# Sensors.net
KiCad netlist of a schematic drawn in Altium Designer
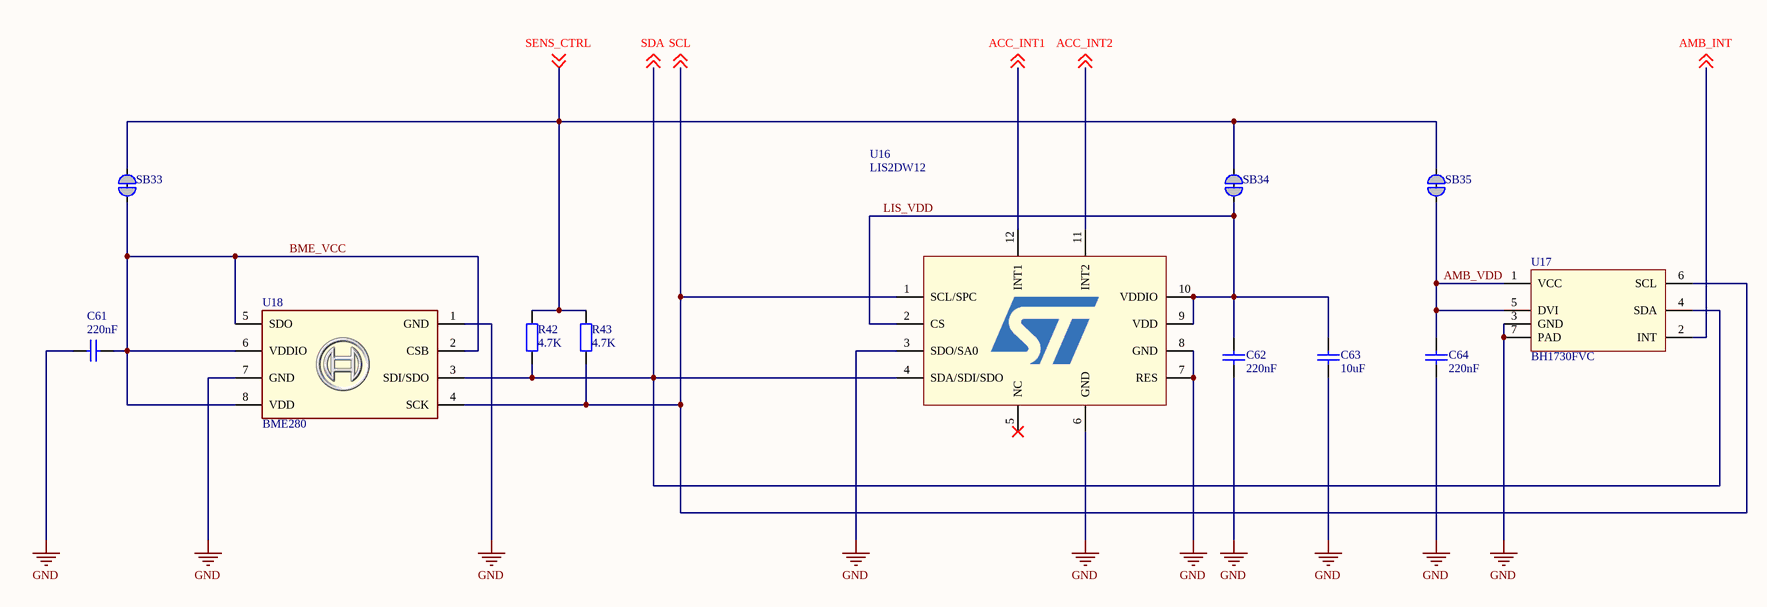
[diagram p0: Sensors.SchDoc]

(export (version "E")
  (design (tool "Eeschema 10.0.6"))
  (components
    (comp (ref "C61")
      (value "220nF")
      (footprint "C0402")
      (description "Capacitor (Semiconductor SIM Model)")
      (fields
        (field (name "MANUFACTURER") "YAGEO")
        (field (name "MANUFACTURER PART NO.") "CC0402KRX5R5BB224")
      )
      (libsource (lib "Miscellaneous Devices") (part "Cap Semi"))
    )
    (comp (ref "C62")
      (value "220nF")
      (footprint "C0402")
      (description "Capacitor (Semiconductor SIM Model)")
      (fields
        (field (name "MANUFACTURER") "YAGEO")
        (field (name "MANUFACTURER PART NO.") "CC0402KRX5R5BB224")
      )
      (libsource (lib "Miscellaneous Devices") (part "Cap Semi"))
    )
    (comp (ref "C63")
      (value "10uF")
      (footprint "C0402")
      (description "Capacitor (Semiconductor SIM Model)")
      (fields
        (field (name "MANUFACTURER") "YAGEO")
        (field (name "MANUFACTURER PART NO.") "CC0402KRX5R5BB224")
      )
      (libsource (lib "Miscellaneous Devices") (part "Cap Semi"))
    )
    (comp (ref "C64")
      (value "220nF")
      (footprint "C0402")
      (description "Capacitor (Semiconductor SIM Model)")
      (fields
        (field (name "MANUFACTURER") "YAGEO")
        (field (name "MANUFACTURER PART NO.") "CC0402KRX5R5BB224")
      )
      (libsource (lib "Miscellaneous Devices") (part "Cap Semi"))
    )
    (comp (ref "R42")
      (value "4.7K")
      (footprint "R0402")
      (fields
        (field (name "MANUFACTURER") "ASJ")
        (field (name "MANUFACTURER PART NO.") "CR10-472-JK")
        (field (name "Comment") "Res2")
      )
      (libsource (lib "Miscellaneous Devices") (part "Res2"))
    )
    (comp (ref "R43")
      (value "4.7K")
      (footprint "R0402")
      (fields
        (field (name "MANUFACTURER") "ASJ")
        (field (name "MANUFACTURER PART NO.") "CR10-472-JK")
        (field (name "Comment") "Res2")
      )
      (libsource (lib "Miscellaneous Devices") (part "Res2"))
    )
    (comp (ref "SB33")
      (value "Solderbridge")
      (footprint "Solderbridge_Shorted")
      (libsource (lib "altium-import") (part "root_1_SOLDERBRIDGE_SHORTED_"))
    )
    (comp (ref "SB34")
      (value "Solderbridge")
      (footprint "Solderbridge_Shorted")
      (libsource (lib "altium-import") (part "root_1_SOLDERBRIDGE_SHORTED_"))
    )
    (comp (ref "SB35")
      (value "Solderbridge")
      (footprint "Solderbridge_Shorted")
      (libsource (lib "altium-import") (part "root_1_SOLDERBRIDGE_SHORTED_"))
    )
    (comp (ref "U16")
      (value "LIS2DW12")
      (footprint "LGA-12 package")
      (fields
        (field (name "MANUFACTURER") "STMicroelectronics")
        (field (name "MANUFACTURER PART NO.") "LIS2DW12TR")
      )
      (libsource (lib "LIS2DW12") (part "LIS2DW12"))
    )
    (comp (ref "U17")
      (value "BH1730FVC")
      (footprint "WSOF6")
      (description "Digital 16bit Serial Output Type Ambient Light Sensor IC")
      (fields (field (name "MANUFACTURER") "ROHM") (field (name "MANUFACTURER PART NO.") "BH1730FVC-TR"))
      (libsource (lib "RUT2CLOUDPrjPcb") (part "BH1730FVC"))
    )
    (comp (ref "U18")
      (value "BME280")
      (footprint "BME280")
      (fields (field (name "MANUFACTURER") "BOSH"))
      (libsource (lib "RUT2CLOUDPrjPcb") (part "BME280"))
    )
  )
  (nets
    (net (code "1") (name "/AMB_VDD") (class "Default")
      (node (ref "C64") (pin "1") (pinfunction "1_1") (pintype "passive"))
      (node (ref "SB35") (pin "2") (pinfunction "1_2") (pintype "passive"))
      (node (ref "U17") (pin "1") (pinfunction "VCC_1") (pintype "passive"))
      (node (ref "U17") (pin "5") (pinfunction "DVI_5") (pintype "passive"))
    )
    (net (code "2") (name "/BME_VCC") (class "Default")
      (node (ref "C61") (pin "1") (pinfunction "1_1") (pintype "passive"))
      (node (ref "SB33") (pin "2") (pinfunction "1_2") (pintype "passive"))
      (node (ref "U18") (pin "2") (pinfunction "CSB_2") (pintype "passive"))
      (node (ref "U18") (pin "5") (pinfunction "SDO_5") (pintype "passive"))
      (node (ref "U18") (pin "6") (pinfunction "VDDIO_6") (pintype "passive"))
      (node (ref "U18") (pin "8") (pinfunction "VDD_8") (pintype "passive"))
    )
    (net (code "3") (name "/LIS_VDD") (class "Default")
      (node (ref "C62") (pin "1") (pinfunction "1_1") (pintype "passive"))
      (node (ref "C63") (pin "1") (pinfunction "1_1") (pintype "passive"))
      (node (ref "SB34") (pin "2") (pinfunction "1_2") (pintype "passive"))
      (node (ref "U16") (pin "10") (pinfunction "VDDIO_10") (pintype "passive"))
      (node (ref "U16") (pin "2") (pinfunction "CS_2") (pintype "passive"))
      (node (ref "U16") (pin "9") (pinfunction "VDD_9") (pintype "passive"))
    )
    (net (code "4") (name "ACC_INT1") (class "Default")
      (node (ref "U16") (pin "12") (pinfunction "INT1_12") (pintype "passive"))
    )
    (net (code "5") (name "ACC_INT2") (class "Default")
      (node (ref "U16") (pin "11") (pinfunction "INT2_11") (pintype "passive"))
    )
    (net (code "6") (name "AMB_INT") (class "Default")
      (node (ref "U17") (pin "2") (pinfunction "INT_2") (pintype "passive"))
    )
    (net (code "7") (name "GND") (class "Default")
      (node (ref "C61") (pin "2") (pinfunction "2_2") (pintype "passive"))
      (node (ref "C62") (pin "2") (pinfunction "2_2") (pintype "passive"))
      (node (ref "C63") (pin "2") (pinfunction "2_2") (pintype "passive"))
      (node (ref "C64") (pin "2") (pinfunction "2_2") (pintype "passive"))
      (node (ref "U16") (pin "3") (pinfunction "SDO/SA0_3") (pintype "passive"))
      (node (ref "U16") (pin "6") (pinfunction "GND_6") (pintype "passive"))
      (node (ref "U16") (pin "7") (pinfunction "RES_7") (pintype "passive"))
      (node (ref "U16") (pin "8") (pinfunction "GND_8") (pintype "passive"))
      (node (ref "U17") (pin "3") (pinfunction "GND_3") (pintype "passive"))
      (node (ref "U17") (pin "7") (pinfunction "PAD_7") (pintype "passive"))
      (node (ref "U18") (pin "1") (pinfunction "GND_1") (pintype "passive"))
      (node (ref "U18") (pin "7") (pinfunction "GND_7") (pintype "passive"))
    )
    (net (code "8") (name "SCL") (class "Default")
      (node (ref "R43") (pin "2") (pinfunction "2_2") (pintype "passive"))
      (node (ref "U16") (pin "1") (pinfunction "SCL/SPC_1") (pintype "passive"))
      (node (ref "U17") (pin "6") (pinfunction "SCL_6") (pintype "passive"))
      (node (ref "U18") (pin "4") (pinfunction "SCK_4") (pintype "passive"))
    )
    (net (code "9") (name "SDA") (class "Default")
      (node (ref "R42") (pin "2") (pinfunction "2_2") (pintype "passive"))
      (node (ref "U16") (pin "4") (pinfunction "SDA/SDI/SDO_4") (pintype "passive"))
      (node (ref "U17") (pin "4") (pinfunction "SDA_4") (pintype "passive"))
      (node (ref "U18") (pin "3") (pinfunction "SDI/SDO_3") (pintype "passive"))
    )
    (net (code "10") (name "SENS_CTRL") (class "Default")
      (node (ref "R42") (pin "1") (pinfunction "1_1") (pintype "passive"))
      (node (ref "R43") (pin "1") (pinfunction "1_1") (pintype "passive"))
      (node (ref "SB33") (pin "1") (pinfunction "0_1") (pintype "passive"))
      (node (ref "SB34") (pin "1") (pinfunction "0_1") (pintype "passive"))
      (node (ref "SB35") (pin "1") (pinfunction "0_1") (pintype "passive"))
    )
    (net (code "11") (name "unconnected-(U16-NC-Pad5)") (class "Default")
      (node (ref "U16") (pin "5") (pinfunction "NC_5") (pintype "passive+no_connect"))
    )
  )
)
